# blink1mk2_v2e.net
KiCad netlist of a schematic drawn in EAGLE
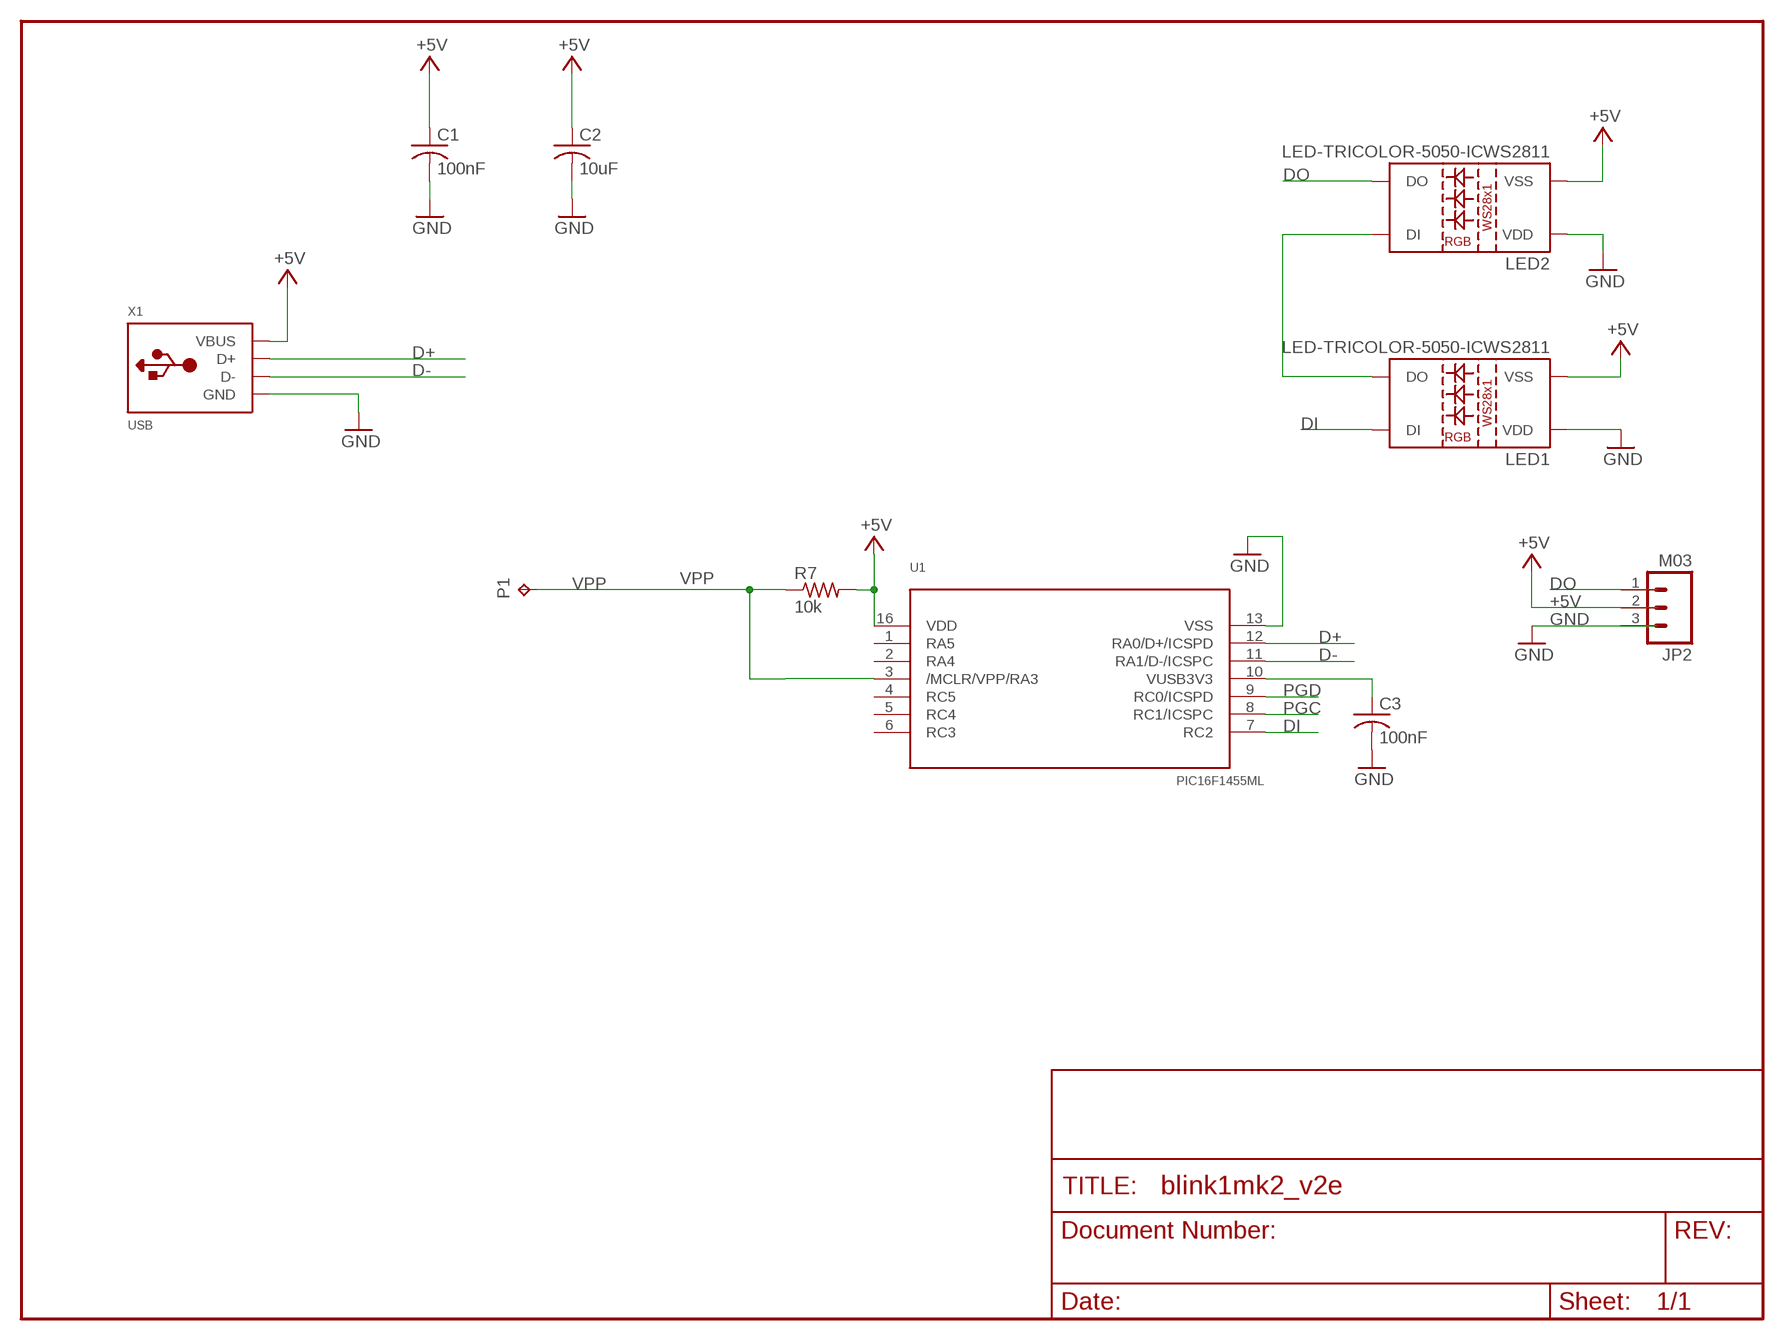
[diagram p0: schematic, sheet 1]

(export (version "E")
  (design (tool "Eeschema 10.0.6"))
  (components
    (comp (ref "C1")
      (value "100nF")
      (footprint "eagle-import:C0603")
      (libsource (lib "eagle-import") (part "C-USC0603"))
    )
    (comp (ref "C2")
      (value "10uF")
      (footprint "eagle-import:C0603")
      (libsource (lib "eagle-import") (part "C-USC0603"))
    )
    (comp (ref "C3")
      (value "100nF")
      (footprint "eagle-import:C0603")
      (libsource (lib "eagle-import") (part "C-USC0603"))
    )
    (comp (ref "JP2")
      (value "M03")
      (footprint "eagle-import:1X03-1.27MM")
      (libsource (lib "eagle-import") (part "M03"))
    )
    (comp (ref "LED1")
      (value "LED-TRICOLOR-5050-ICWS2811")
      (footprint "eagle-import:LED-TRICOLOR-5050-IC")
      (libsource (lib "eagle-import") (part "LED-TRICOLOR-5050-ICWS2811"))
    )
    (comp (ref "LED2")
      (value "LED-TRICOLOR-5050-ICWS2811")
      (footprint "eagle-import:LED-TRICOLOR-5050-IC")
      (libsource (lib "eagle-import") (part "LED-TRICOLOR-5050-ICWS2811"))
    )
    (comp (ref "P1")
      (value "TPTP11SQ")
      (footprint "eagle-import:TP11SQ")
      (libsource (lib "eagle-import") (part "TPTP11SQ"))
    )
    (comp (ref "R7")
      (value "10k")
      (footprint "eagle-import:R0603")
      (libsource (lib "eagle-import") (part "R-US_R0603"))
    )
    (comp (ref "U1")
      (value "PIC16F1455ML")
      (footprint "eagle-import:QFN16_4X4")
      (libsource (lib "eagle-import") (part "PIC16F1455ML"))
    )
    (comp (ref "X1")
      (value "USB")
      (footprint "eagle-import:MOLEX-48037-1000")
      (libsource (lib "eagle-import") (part "USB"))
    )
  )
  (nets
    (net (code "1") (name "+5V") (class "Default")
      (node (ref "C1") (pin "1") (pinfunction "1_1") (pintype "passive"))
      (node (ref "C2") (pin "1") (pinfunction "1_1") (pintype "passive"))
      (node (ref "JP2") (pin "2") (pinfunction "2_2") (pintype "passive"))
      (node (ref "LED1") (pin "6") (pinfunction "VSS_6") (pintype "bidirectional"))
      (node (ref "LED2") (pin "6") (pinfunction "VSS_6") (pintype "bidirectional"))
      (node (ref "R7") (pin "2") (pinfunction "2_2") (pintype "passive"))
      (node (ref "U1") (pin "16") (pinfunction "VDD_16") (pintype "bidirectional"))
      (node (ref "X1") (pin "1") (pinfunction "VBUS_1") (pintype "power_in"))
    )
    (net (code "2") (name "/D+") (class "Default")
      (node (ref "U1") (pin "12") (pinfunction "RA0/D+/ICSPD_12") (pintype "bidirectional"))
      (node (ref "X1") (pin "3") (pinfunction "D+_3") (pintype "bidirectional"))
    )
    (net (code "3") (name "/D-") (class "Default")
      (node (ref "U1") (pin "11") (pinfunction "RA1/D-/ICSPC_11") (pintype "bidirectional"))
      (node (ref "X1") (pin "2") (pinfunction "D-_2") (pintype "bidirectional"))
    )
    (net (code "4") (name "/DI") (class "Default")
      (node (ref "LED1") (pin "2") (pinfunction "DI_2") (pintype "bidirectional"))
      (node (ref "U1") (pin "7") (pinfunction "RC2_7") (pintype "bidirectional"))
    )
    (net (code "5") (name "/DO") (class "Default")
      (node (ref "JP2") (pin "1") (pinfunction "1_1") (pintype "passive"))
      (node (ref "LED2") (pin "1") (pinfunction "DO_1") (pintype "bidirectional"))
    )
    (net (code "6") (name "/PGC") (class "Default")
      (node (ref "U1") (pin "8") (pinfunction "RC1/ICSPC_8") (pintype "bidirectional"))
    )
    (net (code "7") (name "/PGD") (class "Default")
      (node (ref "U1") (pin "9") (pinfunction "RC0/ICSPD_9") (pintype "bidirectional"))
    )
    (net (code "8") (name "/VPP") (class "Default")
      (node (ref "P1") (pin "TP") (pinfunction "TP_TP") (pintype "input"))
      (node (ref "R7") (pin "1") (pinfunction "1_1") (pintype "passive"))
      (node (ref "U1") (pin "3") (pinfunction "/MCLR/VPP/RA3_3") (pintype "bidirectional"))
    )
    (net (code "9") (name "GND") (class "Default")
      (node (ref "C1") (pin "2") (pinfunction "2_2") (pintype "passive"))
      (node (ref "C2") (pin "2") (pinfunction "2_2") (pintype "passive"))
      (node (ref "C3") (pin "2") (pinfunction "2_2") (pintype "passive"))
      (node (ref "JP2") (pin "3") (pinfunction "3_3") (pintype "passive"))
      (node (ref "LED1") (pin "3") (pinfunction "VDD_3") (pintype "bidirectional"))
      (node (ref "LED1") (pin "5") (pinfunction "VDD_5") (pintype "bidirectional"))
      (node (ref "LED2") (pin "3") (pinfunction "VDD_3") (pintype "bidirectional"))
      (node (ref "LED2") (pin "5") (pinfunction "VDD_5") (pintype "bidirectional"))
      (node (ref "U1") (pin "13") (pinfunction "VSS_13") (pintype "bidirectional"))
      (node (ref "X1") (pin "4") (pinfunction "GND_4") (pintype "power_in"))
    )
    (net (code "10") (name "Net-(LED1-DO)") (class "Default")
      (node (ref "LED1") (pin "1") (pinfunction "DO_1") (pintype "bidirectional"))
      (node (ref "LED2") (pin "2") (pinfunction "DI_2") (pintype "bidirectional"))
    )
    (net (code "11") (name "Net-(U1-VUSB3V3)") (class "Default")
      (node (ref "C3") (pin "1") (pinfunction "1_1") (pintype "passive"))
      (node (ref "U1") (pin "10") (pinfunction "VUSB3V3_10") (pintype "bidirectional"))
    )
    (net (code "12") (name "unconnected-(U1-RA4-Pad2)") (class "Default")
      (node (ref "U1") (pin "2") (pinfunction "RA4_2") (pintype "bidirectional"))
    )
    (net (code "13") (name "unconnected-(U1-RA5-Pad1)") (class "Default")
      (node (ref "U1") (pin "1") (pinfunction "RA5_1") (pintype "bidirectional"))
    )
    (net (code "14") (name "unconnected-(U1-RC3-Pad6)") (class "Default")
      (node (ref "U1") (pin "6") (pinfunction "RC3_6") (pintype "bidirectional"))
    )
    (net (code "15") (name "unconnected-(U1-RC4-Pad5)") (class "Default")
      (node (ref "U1") (pin "5") (pinfunction "RC4_5") (pintype "bidirectional"))
    )
    (net (code "16") (name "unconnected-(U1-RC5-Pad4)") (class "Default")
      (node (ref "U1") (pin "4") (pinfunction "RC5_4") (pintype "bidirectional"))
    )
  )
)
